# SeniorDesignTest.net
KiCad netlist of a schematic drawn in EAGLE
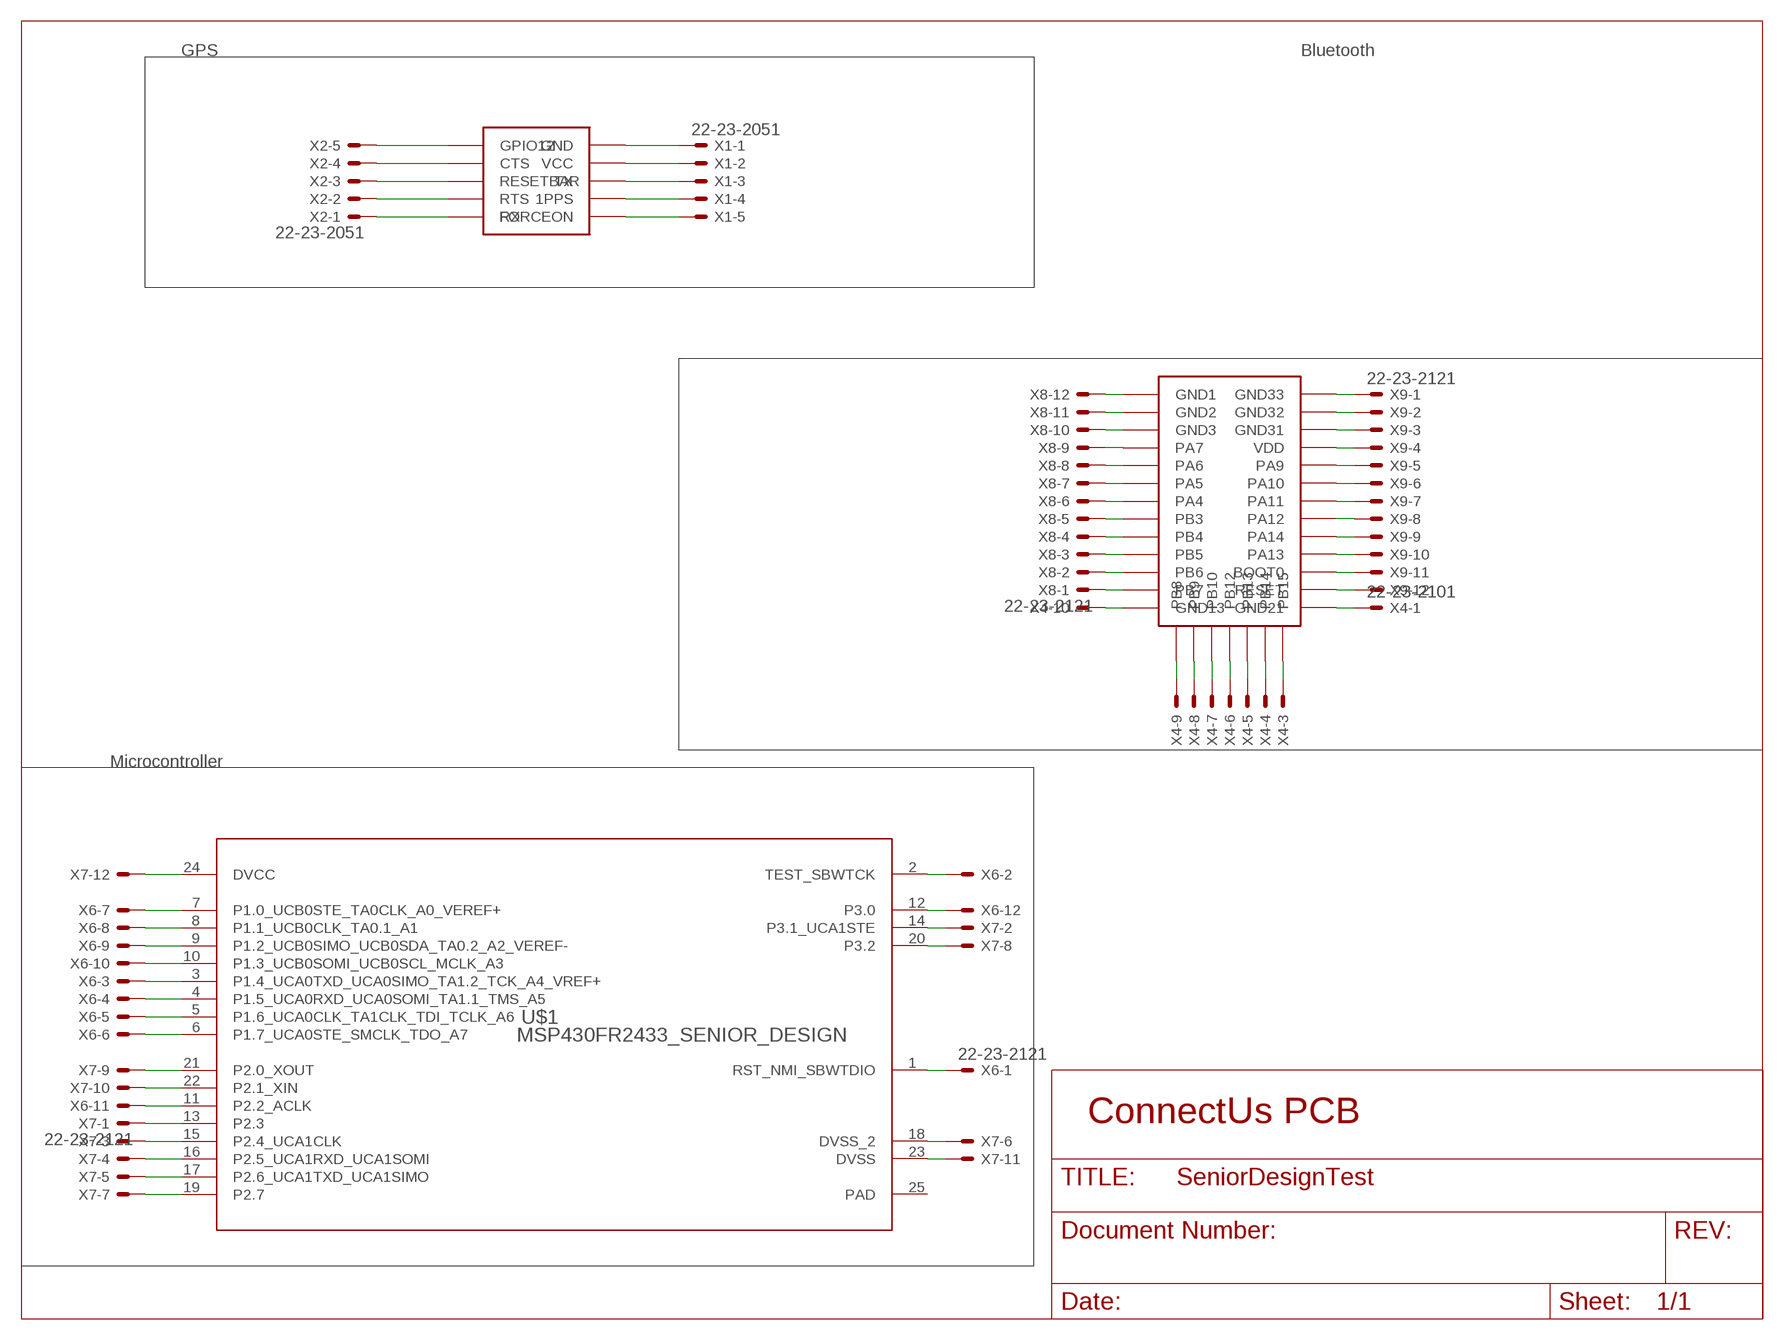
[diagram p0: schematic, sheet 1]

(export (version "E")
  (design (tool "Eeschema 10.0.6"))
  (components
    (comp (ref "GPS(ORG1510)")
      (value "ORG1510")
      (footprint "eagle-import:ORG1510")
      (libsource (lib "eagle-import") (part "ORG1510"))
    )
    (comp (ref "U$1")
      (value "MSP430FR2433_SENIOR_DESIGN")
      (footprint "eagle-import:RGE0024G_NV")
      (libsource (lib "eagle-import") (part "MSP430FR2433_SENIOR_DESIGN"))
    )
    (comp (ref "U$2")
      (value "BT121")
      (footprint "eagle-import:BT121")
      (libsource (lib "eagle-import") (part "BT121"))
    )
    (comp (ref "X1")
      (value "22-23-2051")
      (footprint "eagle-import:22-23-2051")
      (fields (field (name "MF") "MOLEX"))
      (libsource (lib "eagle-import") (part "22-23-2051"))
    )
    (comp (ref "X2")
      (value "22-23-2051")
      (footprint "eagle-import:22-23-2051")
      (fields (field (name "MF") "MOLEX"))
      (libsource (lib "eagle-import") (part "22-23-2051"))
    )
    (comp (ref "X4")
      (value "22-23-2101")
      (footprint "eagle-import:22-23-2101")
      (fields (field (name "MF") "MOLEX"))
      (libsource (lib "eagle-import") (part "22-23-2101"))
    )
    (comp (ref "X6")
      (value "22-23-2121")
      (footprint "eagle-import:22-23-2121")
      (fields (field (name "MF") "MOLEX"))
      (libsource (lib "eagle-import") (part "22-23-2121"))
    )
    (comp (ref "X7")
      (value "22-23-2121")
      (footprint "eagle-import:22-23-2121")
      (fields (field (name "MF") "MOLEX"))
      (libsource (lib "eagle-import") (part "22-23-2121"))
    )
    (comp (ref "X8")
      (value "22-23-2121")
      (footprint "eagle-import:22-23-2121")
      (fields (field (name "MF") "MOLEX"))
      (libsource (lib "eagle-import") (part "22-23-2121"))
    )
    (comp (ref "X9")
      (value "22-23-2121")
      (footprint "eagle-import:22-23-2121")
      (fields (field (name "MF") "MOLEX"))
      (libsource (lib "eagle-import") (part "22-23-2121"))
    )
  )
  (nets
    (net (code "1") (name "/PAD") (class "Default")
      (node (ref "U$1") (pin "25") (pinfunction "PAD_25") (pintype "power_in"))
    )
    (net (code "2") (name "Net-(U$1-DVCC)") (class "Default")
      (node (ref "U$1") (pin "24") (pinfunction "DVCC_24") (pintype "power_in"))
      (node (ref "X7") (pin "12") (pinfunction "S_12") (pintype "passive"))
    )
    (net (code "3") (name "Net-(U$1-DVSS)") (class "Default")
      (node (ref "U$1") (pin "23") (pinfunction "DVSS_23") (pintype "power_in"))
      (node (ref "X7") (pin "11") (pinfunction "S_11") (pintype "passive"))
    )
    (net (code "4") (name "Net-(U$1-DVSS_2)") (class "Default")
      (node (ref "U$1") (pin "18") (pinfunction "DVSS_2_18") (pintype "power_in"))
      (node (ref "X7") (pin "6") (pinfunction "S_6") (pintype "passive"))
    )
    (net (code "5") (name "Net-(U$1-P1.0_UCB0STE_TA0CLK_A0_VEREF+)") (class "Default")
      (node (ref "U$1") (pin "7") (pinfunction "P1.0_UCB0STE_TA0CLK_A0_VEREF+_7") (pintype "bidirectional"))
      (node (ref "X6") (pin "7") (pinfunction "S_7") (pintype "passive"))
    )
    (net (code "6") (name "Net-(U$1-P1.1_UCB0CLK_TA0.1_A1)") (class "Default")
      (node (ref "U$1") (pin "8") (pinfunction "P1.1_UCB0CLK_TA0.1_A1_8") (pintype "bidirectional"))
      (node (ref "X6") (pin "8") (pinfunction "S_8") (pintype "passive"))
    )
    (net (code "7") (name "Net-(U$1-P1.2_UCB0SIMO_UCB0SDA_TA0.2_A2_VEREF-)") (class "Default")
      (node (ref "U$1") (pin "9") (pinfunction "P1.2_UCB0SIMO_UCB0SDA_TA0.2_A2_VEREF-_9") (pintype "bidirectional"))
      (node (ref "X6") (pin "9") (pinfunction "S_9") (pintype "passive"))
    )
    (net (code "8") (name "Net-(U$1-P1.3_UCB0SOMI_UCB0SCL_MCLK_A3)") (class "Default")
      (node (ref "U$1") (pin "10") (pinfunction "P1.3_UCB0SOMI_UCB0SCL_MCLK_A3_10") (pintype "bidirectional"))
      (node (ref "X6") (pin "10") (pinfunction "S_10") (pintype "passive"))
    )
    (net (code "9") (name "Net-(U$1-P1.4_UCA0TXD_UCA0SIMO_TA1.2_TCK_A4_VREF+)") (class "Default")
      (node (ref "U$1") (pin "3") (pinfunction "P1.4_UCA0TXD_UCA0SIMO_TA1.2_TCK_A4_VREF+_3") (pintype "bidirectional"))
      (node (ref "X6") (pin "3") (pinfunction "S_3") (pintype "passive"))
    )
    (net (code "10") (name "Net-(U$1-P1.5_UCA0RXD_UCA0SOMI_TA1.1_TMS_A5)") (class "Default")
      (node (ref "U$1") (pin "4") (pinfunction "P1.5_UCA0RXD_UCA0SOMI_TA1.1_TMS_A5_4") (pintype "bidirectional"))
      (node (ref "X6") (pin "4") (pinfunction "S_4") (pintype "passive"))
    )
    (net (code "11") (name "Net-(U$1-P1.6_UCA0CLK_TA1CLK_TDI_TCLK_A6)") (class "Default")
      (node (ref "U$1") (pin "5") (pinfunction "P1.6_UCA0CLK_TA1CLK_TDI_TCLK_A6_5") (pintype "bidirectional"))
      (node (ref "X6") (pin "5") (pinfunction "S_5") (pintype "passive"))
    )
    (net (code "12") (name "Net-(U$1-P1.7_UCA0STE_SMCLK_TDO_A7)") (class "Default")
      (node (ref "U$1") (pin "6") (pinfunction "P1.7_UCA0STE_SMCLK_TDO_A7_6") (pintype "bidirectional"))
      (node (ref "X6") (pin "6") (pinfunction "S_6") (pintype "passive"))
    )
    (net (code "13") (name "Net-(U$1-P2.0_XOUT)") (class "Default")
      (node (ref "U$1") (pin "21") (pinfunction "P2.0_XOUT_21") (pintype "bidirectional"))
      (node (ref "X7") (pin "9") (pinfunction "S_9") (pintype "passive"))
    )
    (net (code "14") (name "Net-(U$1-P2.1_XIN)") (class "Default")
      (node (ref "U$1") (pin "22") (pinfunction "P2.1_XIN_22") (pintype "bidirectional"))
      (node (ref "X7") (pin "10") (pinfunction "S_10") (pintype "passive"))
    )
    (net (code "15") (name "Net-(U$1-P2.2_ACLK)") (class "Default")
      (node (ref "U$1") (pin "11") (pinfunction "P2.2_ACLK_11") (pintype "bidirectional"))
      (node (ref "X6") (pin "11") (pinfunction "S_11") (pintype "passive"))
    )
    (net (code "16") (name "Net-(U$1-P2.3)") (class "Default")
      (node (ref "U$1") (pin "13") (pinfunction "P2.3_13") (pintype "bidirectional"))
      (node (ref "X7") (pin "1") (pinfunction "S_1") (pintype "passive"))
    )
    (net (code "17") (name "Net-(U$1-P2.4_UCA1CLK)") (class "Default")
      (node (ref "U$1") (pin "15") (pinfunction "P2.4_UCA1CLK_15") (pintype "bidirectional"))
      (node (ref "X7") (pin "3") (pinfunction "S_3") (pintype "passive"))
    )
    (net (code "18") (name "Net-(U$1-P2.5_UCA1RXD_UCA1SOMI)") (class "Default")
      (node (ref "U$1") (pin "16") (pinfunction "P2.5_UCA1RXD_UCA1SOMI_16") (pintype "bidirectional"))
      (node (ref "X7") (pin "4") (pinfunction "S_4") (pintype "passive"))
    )
    (net (code "19") (name "Net-(U$1-P2.6_UCA1TXD_UCA1SIMO)") (class "Default")
      (node (ref "U$1") (pin "17") (pinfunction "P2.6_UCA1TXD_UCA1SIMO_17") (pintype "bidirectional"))
      (node (ref "X7") (pin "5") (pinfunction "S_5") (pintype "passive"))
    )
    (net (code "20") (name "Net-(U$1-P2.7)") (class "Default")
      (node (ref "U$1") (pin "19") (pinfunction "P2.7_19") (pintype "bidirectional"))
      (node (ref "X7") (pin "7") (pinfunction "S_7") (pintype "passive"))
    )
    (net (code "21") (name "Net-(U$1-P3.0)") (class "Default")
      (node (ref "U$1") (pin "12") (pinfunction "P3.0_12") (pintype "bidirectional"))
      (node (ref "X6") (pin "12") (pinfunction "S_12") (pintype "passive"))
    )
    (net (code "22") (name "Net-(U$1-P3.1_UCA1STE)") (class "Default")
      (node (ref "U$1") (pin "14") (pinfunction "P3.1_UCA1STE_14") (pintype "bidirectional"))
      (node (ref "X7") (pin "2") (pinfunction "S_2") (pintype "passive"))
    )
    (net (code "23") (name "Net-(U$1-P3.2)") (class "Default")
      (node (ref "U$1") (pin "20") (pinfunction "P3.2_20") (pintype "bidirectional"))
      (node (ref "X7") (pin "8") (pinfunction "S_8") (pintype "passive"))
    )
    (net (code "24") (name "Net-(U$1-RST_NMI_SBWTDIO)") (class "Default")
      (node (ref "U$1") (pin "1") (pinfunction "RST_NMI_SBWTDIO_1") (pintype "bidirectional"))
      (node (ref "X6") (pin "1") (pinfunction "S_1") (pintype "passive"))
    )
    (net (code "25") (name "Net-(U$1-TEST_SBWTCK)") (class "Default")
      (node (ref "U$1") (pin "2") (pinfunction "TEST_SBWTCK_2") (pintype "input"))
      (node (ref "X6") (pin "2") (pinfunction "S_2") (pintype "passive"))
    )
    (net (code "26") (name "Net-(X1A-S)") (class "Default")
      (node (ref "GPS(ORG1510)") (pin "GND") (pinfunction "GND_GND") (pintype "bidirectional"))
      (node (ref "X1") (pin "1") (pinfunction "S_1") (pintype "passive"))
    )
    (net (code "27") (name "Net-(X1B-S)") (class "Default")
      (node (ref "GPS(ORG1510)") (pin "VCC") (pinfunction "VCC_VCC") (pintype "bidirectional"))
      (node (ref "X1") (pin "2") (pinfunction "S_2") (pintype "passive"))
    )
    (net (code "28") (name "Net-(X1C-S)") (class "Default")
      (node (ref "GPS(ORG1510)") (pin "TX") (pinfunction "TX_TX") (pintype "bidirectional"))
      (node (ref "X1") (pin "3") (pinfunction "S_3") (pintype "passive"))
    )
    (net (code "29") (name "Net-(X1D-S)") (class "Default")
      (node (ref "GPS(ORG1510)") (pin "1PPS") (pinfunction "1PPS_1PPS") (pintype "bidirectional"))
      (node (ref "X1") (pin "4") (pinfunction "S_4") (pintype "passive"))
    )
    (net (code "30") (name "Net-(X1E-S)") (class "Default")
      (node (ref "GPS(ORG1510)") (pin "FORCEON") (pinfunction "FORCEON_FORCEON") (pintype "bidirectional"))
      (node (ref "X1") (pin "5") (pinfunction "S_5") (pintype "passive"))
    )
    (net (code "31") (name "Net-(X2A-S)") (class "Default")
      (node (ref "GPS(ORG1510)") (pin "RX") (pinfunction "RX_RX") (pintype "bidirectional"))
      (node (ref "X2") (pin "1") (pinfunction "S_1") (pintype "passive"))
    )
    (net (code "32") (name "Net-(X2B-S)") (class "Default")
      (node (ref "GPS(ORG1510)") (pin "RTS") (pinfunction "RTS_RTS") (pintype "bidirectional"))
      (node (ref "X2") (pin "2") (pinfunction "S_2") (pintype "passive"))
    )
    (net (code "33") (name "Net-(X2C-S)") (class "Default")
      (node (ref "GPS(ORG1510)") (pin "RESETBAR") (pinfunction "RESETBAR_RESETBAR") (pintype "bidirectional"))
      (node (ref "X2") (pin "3") (pinfunction "S_3") (pintype "passive"))
    )
    (net (code "34") (name "Net-(X2D-S)") (class "Default")
      (node (ref "GPS(ORG1510)") (pin "CTS") (pinfunction "CTS_CTS") (pintype "bidirectional"))
      (node (ref "X2") (pin "4") (pinfunction "S_4") (pintype "passive"))
    )
    (net (code "35") (name "Net-(X2E-S)") (class "Default")
      (node (ref "GPS(ORG1510)") (pin "GPIO12") (pinfunction "GPIO12_GPIO12") (pintype "bidirectional"))
      (node (ref "X2") (pin "5") (pinfunction "S_5") (pintype "passive"))
    )
    (net (code "36") (name "Net-(X4A-S)") (class "Default")
      (node (ref "U$2") (pin "GND21") (pinfunction "GND21_GND21") (pintype "bidirectional"))
      (node (ref "X4") (pin "1") (pinfunction "S_1") (pintype "passive"))
    )
    (net (code "37") (name "Net-(X4B-S)") (class "Default")
      (node (ref "U$2") (pin "GND13") (pinfunction "GND13_GND13") (pintype "bidirectional"))
      (node (ref "X4") (pin "10") (pinfunction "S_10") (pintype "passive"))
    )
    (net (code "38") (name "Net-(X4D-S)") (class "Default")
      (node (ref "U$2") (pin "PB15") (pinfunction "PB15_PB15") (pintype "bidirectional"))
      (node (ref "X4") (pin "3") (pinfunction "S_3") (pintype "passive"))
    )
    (net (code "39") (name "Net-(X4E-S)") (class "Default")
      (node (ref "U$2") (pin "PB14") (pinfunction "PB14_PB14") (pintype "bidirectional"))
      (node (ref "X4") (pin "4") (pinfunction "S_4") (pintype "passive"))
    )
    (net (code "40") (name "Net-(X4F-S)") (class "Default")
      (node (ref "U$2") (pin "PB13") (pinfunction "PB13_PB13") (pintype "bidirectional"))
      (node (ref "X4") (pin "5") (pinfunction "S_5") (pintype "passive"))
    )
    (net (code "41") (name "Net-(X4G-S)") (class "Default")
      (node (ref "U$2") (pin "PB12") (pinfunction "PB12_PB12") (pintype "bidirectional"))
      (node (ref "X4") (pin "6") (pinfunction "S_6") (pintype "passive"))
    )
    (net (code "42") (name "Net-(X4H-S)") (class "Default")
      (node (ref "U$2") (pin "PB10") (pinfunction "PB10_PB10") (pintype "bidirectional"))
      (node (ref "X4") (pin "7") (pinfunction "S_7") (pintype "passive"))
    )
    (net (code "43") (name "Net-(X4I-S)") (class "Default")
      (node (ref "U$2") (pin "PB9") (pinfunction "PB9_PB9") (pintype "bidirectional"))
      (node (ref "X4") (pin "8") (pinfunction "S_8") (pintype "passive"))
    )
    (net (code "44") (name "Net-(X4J-S)") (class "Default")
      (node (ref "U$2") (pin "PB8") (pinfunction "PB8_PB8") (pintype "bidirectional"))
      (node (ref "X4") (pin "9") (pinfunction "S_9") (pintype "passive"))
    )
    (net (code "45") (name "Net-(X8A-S)") (class "Default")
      (node (ref "U$2") (pin "PB7") (pinfunction "PB7_PB7") (pintype "bidirectional"))
      (node (ref "X8") (pin "1") (pinfunction "S_1") (pintype "passive"))
    )
    (net (code "46") (name "Net-(X8B-S)") (class "Default")
      (node (ref "U$2") (pin "GND3") (pinfunction "GND3_GND3") (pintype "bidirectional"))
      (node (ref "X8") (pin "10") (pinfunction "S_10") (pintype "passive"))
    )
    (net (code "47") (name "Net-(X8C-S)") (class "Default")
      (node (ref "U$2") (pin "GND2") (pinfunction "GND2_GND2") (pintype "bidirectional"))
      (node (ref "X8") (pin "11") (pinfunction "S_11") (pintype "passive"))
    )
    (net (code "48") (name "Net-(X8D-S)") (class "Default")
      (node (ref "U$2") (pin "GND1") (pinfunction "GND1_GND1") (pintype "bidirectional"))
      (node (ref "X8") (pin "12") (pinfunction "S_12") (pintype "passive"))
    )
    (net (code "49") (name "Net-(X8E-S)") (class "Default")
      (node (ref "U$2") (pin "PB6") (pinfunction "PB6_PB6") (pintype "bidirectional"))
      (node (ref "X8") (pin "2") (pinfunction "S_2") (pintype "passive"))
    )
    (net (code "50") (name "Net-(X8F-S)") (class "Default")
      (node (ref "U$2") (pin "PB5") (pinfunction "PB5_PB5") (pintype "bidirectional"))
      (node (ref "X8") (pin "3") (pinfunction "S_3") (pintype "passive"))
    )
    (net (code "51") (name "Net-(X8G-S)") (class "Default")
      (node (ref "U$2") (pin "PB4") (pinfunction "PB4_PB4") (pintype "bidirectional"))
      (node (ref "X8") (pin "4") (pinfunction "S_4") (pintype "passive"))
    )
    (net (code "52") (name "Net-(X8H-S)") (class "Default")
      (node (ref "U$2") (pin "PB3") (pinfunction "PB3_PB3") (pintype "bidirectional"))
      (node (ref "X8") (pin "5") (pinfunction "S_5") (pintype "passive"))
    )
    (net (code "53") (name "Net-(X8I-S)") (class "Default")
      (node (ref "U$2") (pin "PA4") (pinfunction "PA4_PA4") (pintype "bidirectional"))
      (node (ref "X8") (pin "6") (pinfunction "S_6") (pintype "passive"))
    )
    (net (code "54") (name "Net-(X8J-S)") (class "Default")
      (node (ref "U$2") (pin "PA5") (pinfunction "PA5_PA5") (pintype "bidirectional"))
      (node (ref "X8") (pin "7") (pinfunction "S_7") (pintype "passive"))
    )
    (net (code "55") (name "Net-(X8K-S)") (class "Default")
      (node (ref "U$2") (pin "PA6") (pinfunction "PA6_PA6") (pintype "bidirectional"))
      (node (ref "X8") (pin "8") (pinfunction "S_8") (pintype "passive"))
    )
    (net (code "56") (name "Net-(X8L-S)") (class "Default")
      (node (ref "U$2") (pin "PA7") (pinfunction "PA7_PA7") (pintype "bidirectional"))
      (node (ref "X8") (pin "9") (pinfunction "S_9") (pintype "passive"))
    )
    (net (code "57") (name "Net-(X9A-S)") (class "Default")
      (node (ref "U$2") (pin "GND33") (pinfunction "GND33_GND33") (pintype "bidirectional"))
      (node (ref "X9") (pin "1") (pinfunction "S_1") (pintype "passive"))
    )
    (net (code "58") (name "Net-(X9B-S)") (class "Default")
      (node (ref "U$2") (pin "PA13") (pinfunction "PA13_PA13") (pintype "bidirectional"))
      (node (ref "X9") (pin "10") (pinfunction "S_10") (pintype "passive"))
    )
    (net (code "59") (name "Net-(X9C-S)") (class "Default")
      (node (ref "U$2") (pin "BOOT0") (pinfunction "BOOT0_BOOT0") (pintype "bidirectional"))
      (node (ref "X9") (pin "11") (pinfunction "S_11") (pintype "passive"))
    )
    (net (code "60") (name "Net-(X9D-S)") (class "Default")
      (node (ref "U$2") (pin "RESET") (pinfunction "RESET_RESET") (pintype "bidirectional"))
      (node (ref "X9") (pin "12") (pinfunction "S_12") (pintype "passive"))
    )
    (net (code "61") (name "Net-(X9E-S)") (class "Default")
      (node (ref "U$2") (pin "GND32") (pinfunction "GND32_GND32") (pintype "bidirectional"))
      (node (ref "X9") (pin "2") (pinfunction "S_2") (pintype "passive"))
    )
    (net (code "62") (name "Net-(X9F-S)") (class "Default")
      (node (ref "U$2") (pin "GND31") (pinfunction "GND31_GND31") (pintype "bidirectional"))
      (node (ref "X9") (pin "3") (pinfunction "S_3") (pintype "passive"))
    )
    (net (code "63") (name "Net-(X9G-S)") (class "Default")
      (node (ref "U$2") (pin "VDD") (pinfunction "VDD_VDD") (pintype "bidirectional"))
      (node (ref "X9") (pin "4") (pinfunction "S_4") (pintype "passive"))
    )
    (net (code "64") (name "Net-(X9H-S)") (class "Default")
      (node (ref "U$2") (pin "PA9") (pinfunction "PA9_PA9") (pintype "bidirectional"))
      (node (ref "X9") (pin "5") (pinfunction "S_5") (pintype "passive"))
    )
    (net (code "65") (name "Net-(X9I-S)") (class "Default")
      (node (ref "U$2") (pin "PA10") (pinfunction "PA10_PA10") (pintype "bidirectional"))
      (node (ref "X9") (pin "6") (pinfunction "S_6") (pintype "passive"))
    )
    (net (code "66") (name "Net-(X9J-S)") (class "Default")
      (node (ref "U$2") (pin "PA11") (pinfunction "PA11_PA11") (pintype "bidirectional"))
      (node (ref "X9") (pin "7") (pinfunction "S_7") (pintype "passive"))
    )
    (net (code "67") (name "Net-(X9K-S)") (class "Default")
      (node (ref "U$2") (pin "PA12") (pinfunction "PA12_PA12") (pintype "bidirectional"))
      (node (ref "X9") (pin "8") (pinfunction "S_8") (pintype "passive"))
    )
    (net (code "68") (name "Net-(X9L-S)") (class "Default")
      (node (ref "U$2") (pin "PA14") (pinfunction "PA14_PA14") (pintype "bidirectional"))
      (node (ref "X9") (pin "9") (pinfunction "S_9") (pintype "passive"))
    )
  )
)
